# Fingerprint.net
KiCad netlist of a schematic drawn in EAGLE
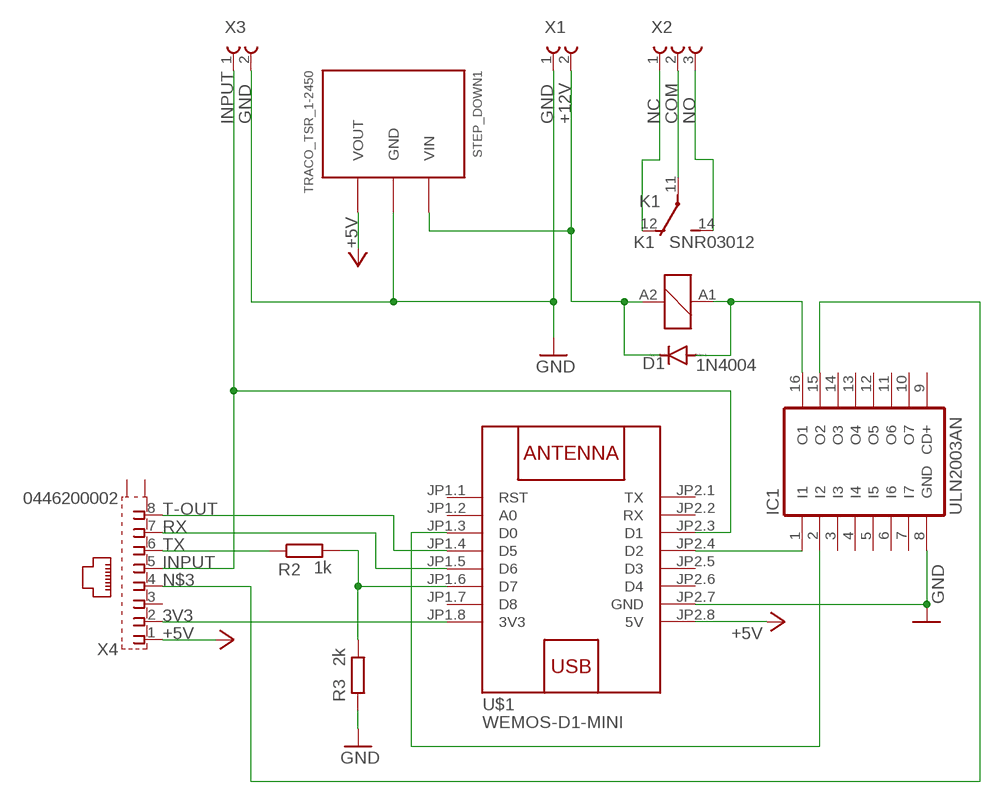
[diagram p0: schematic, sheet 1]

(export (version "E")
  (design (tool "Eeschema 10.0.6"))
  (components
    (comp (ref "D1")
      (value "1N4004")
      (footprint "eagle-import:DO41-10")
      (libsource (lib "eagle-import") (part "1N4004"))
    )
    (comp (ref "IC1")
      (value "ULN2003AN")
      (footprint "eagle-import:DIL16")
      (libsource (lib "eagle-import") (part "ULN2003AN"))
    )
    (comp (ref "K1")
      (value "SNR03012")
      (footprint "eagle-import:SNR-V")
      (libsource (lib "eagle-import") (part "SNR?03012"))
    )
    (comp (ref "R2")
      (value "1k")
      (footprint "eagle-import:0207_10")
      (libsource (lib "eagle-import") (part "R-EU_0207/10"))
    )
    (comp (ref "R3")
      (value "2k")
      (footprint "eagle-import:0207_10")
      (libsource (lib "eagle-import") (part "R-EU_0207/10"))
    )
    (comp (ref "STEP_DOWN1")
      (value "TRACO_TSR_1-2450")
      (footprint "eagle-import:TRACO_TSR_1-2450")
      (libsource (lib "eagle-import") (part "TRACO_TSR_1-2450"))
    )
    (comp (ref "U$1")
      (value "WEMOS-D1-MINI")
      (footprint "eagle-import:WEMOS-D1-MINI")
      (libsource (lib "eagle-import") (part "WEMOS-D1-MINI"))
    )
    (comp (ref "X1")
      (value "2PIN_5MM_TERMINAL")
      (footprint "eagle-import:2PIN_5MM_TERMMINAL")
      (libsource (lib "eagle-import") (part "2PIN_5MM_TERMINAL"))
    )
    (comp (ref "X2")
      (value "3PIN_5MM_TERMINAL")
      (footprint "eagle-import:3PIN_5MM_TERMINAL")
      (libsource (lib "eagle-import") (part "3PIN_5MM_TERMINAL"))
    )
    (comp (ref "X3")
      (value "2PIN_5MM_TERMINAL")
      (footprint "eagle-import:2PIN_5MM_TERMMINAL")
      (libsource (lib "eagle-import") (part "2PIN_5MM_TERMINAL"))
    )
    (comp (ref "X4")
      (value "0446200002")
      (footprint "eagle-import:0446200002")
      (fields (field (name "MF") "MOLEX"))
      (libsource (lib "eagle-import") (part "0446200002"))
    )
  )
  (nets
    (net (code "1") (name "+5V") (class "Default")
      (node (ref "STEP_DOWN1") (pin "VOUT") (pinfunction "VOUT_VOUT") (pintype "output"))
      (node (ref "U$1") (pin "JP2.8") (pinfunction "5V_JP2.8") (pintype "power_in"))
      (node (ref "X4") (pin "1") (pinfunction "1_1") (pintype "passive"))
    )
    (net (code "2") (name "/+12V") (class "Default")
      (node (ref "D1") (pin "C") (pinfunction "C_C") (pintype "passive"))
      (node (ref "K1") (pin "A2") (pinfunction "2_A2") (pintype "passive"))
      (node (ref "STEP_DOWN1") (pin "VIN") (pinfunction "VIN_VIN") (pintype "input"))
      (node (ref "X1") (pin "2") (pinfunction "2_2") (pintype "passive"))
    )
    (net (code "3") (name "/3V3") (class "Default")
      (node (ref "U$1") (pin "JP1.8") (pinfunction "3V3_JP1.8") (pintype "power_in"))
      (node (ref "X4") (pin "2") (pinfunction "2_2") (pintype "passive"))
    )
    (net (code "4") (name "/COM") (class "Default")
      (node (ref "K1") (pin "11") (pinfunction "P_11") (pintype "passive"))
      (node (ref "X2") (pin "2") (pinfunction "2_2") (pintype "passive"))
    )
    (net (code "5") (name "/INPUT") (class "Default")
      (node (ref "U$1") (pin "JP2.3") (pinfunction "D1_JP2.3") (pintype "bidirectional"))
      (node (ref "X3") (pin "1") (pinfunction "1_1") (pintype "passive"))
      (node (ref "X4") (pin "5") (pinfunction "5_5") (pintype "passive"))
    )
    (net (code "6") (name "/N$3") (class "Default")
      (node (ref "IC1") (pin "15") (pinfunction "O2_15") (pintype "open_collector"))
      (node (ref "X4") (pin "4") (pinfunction "4_4") (pintype "passive"))
    )
    (net (code "7") (name "/NC") (class "Default")
      (node (ref "K1") (pin "12") (pinfunction "O_12") (pintype "passive"))
      (node (ref "X2") (pin "1") (pinfunction "1_1") (pintype "passive"))
    )
    (net (code "8") (name "/NO") (class "Default")
      (node (ref "K1") (pin "14") (pinfunction "S_14") (pintype "passive"))
      (node (ref "X2") (pin "3") (pinfunction "3_3") (pintype "passive"))
    )
    (net (code "9") (name "/RX") (class "Default")
      (node (ref "U$1") (pin "JP1.5") (pinfunction "D6_JP1.5") (pintype "bidirectional"))
      (node (ref "X4") (pin "7") (pinfunction "7_7") (pintype "passive"))
    )
    (net (code "10") (name "/T-OUT") (class "Default")
      (node (ref "U$1") (pin "JP1.4") (pinfunction "D5_JP1.4") (pintype "bidirectional"))
      (node (ref "X4") (pin "8") (pinfunction "8_8") (pintype "passive"))
    )
    (net (code "11") (name "/TX") (class "Default")
      (node (ref "R2") (pin "1") (pinfunction "1_1") (pintype "passive"))
      (node (ref "X4") (pin "6") (pinfunction "6_6") (pintype "passive"))
    )
    (net (code "12") (name "GND") (class "Default")
      (node (ref "IC1") (pin "8") (pinfunction "GND_8") (pintype "power_in"))
      (node (ref "R3") (pin "2") (pinfunction "2_2") (pintype "passive"))
      (node (ref "STEP_DOWN1") (pin "GND") (pinfunction "GND_GND") (pintype "bidirectional"))
      (node (ref "U$1") (pin "JP2.7") (pinfunction "GND_JP2.7") (pintype "power_in"))
      (node (ref "X1") (pin "1") (pinfunction "1_1") (pintype "passive"))
      (node (ref "X3") (pin "2") (pinfunction "2_2") (pintype "passive"))
    )
    (net (code "13") (name "Net-(IC1-I1)") (class "Default")
      (node (ref "IC1") (pin "1") (pinfunction "I1_1") (pintype "input"))
      (node (ref "U$1") (pin "JP2.4") (pinfunction "D2_JP2.4") (pintype "bidirectional"))
    )
    (net (code "14") (name "Net-(IC1-I2)") (class "Default")
      (node (ref "IC1") (pin "2") (pinfunction "I2_2") (pintype "input"))
      (node (ref "U$1") (pin "JP1.3") (pinfunction "D0_JP1.3") (pintype "bidirectional"))
    )
    (net (code "15") (name "Net-(IC1-O1)") (class "Default")
      (node (ref "D1") (pin "A") (pinfunction "A_A") (pintype "passive"))
      (node (ref "IC1") (pin "16") (pinfunction "O1_16") (pintype "open_collector"))
      (node (ref "K1") (pin "A1") (pinfunction "1_A1") (pintype "passive"))
    )
    (net (code "16") (name "Net-(U$1-D7)") (class "Default")
      (node (ref "R2") (pin "2") (pinfunction "2_2") (pintype "passive"))
      (node (ref "R3") (pin "1") (pinfunction "1_1") (pintype "passive"))
      (node (ref "U$1") (pin "JP1.6") (pinfunction "D7_JP1.6") (pintype "bidirectional"))
    )
    (net (code "17") (name "unconnected-(IC1-CD+-Pad9)") (class "Default")
      (node (ref "IC1") (pin "9") (pinfunction "CD+_9") (pintype "passive"))
    )
    (net (code "18") (name "unconnected-(IC1-I3-Pad3)") (class "Default")
      (node (ref "IC1") (pin "3") (pinfunction "I3_3") (pintype "input"))
    )
    (net (code "19") (name "unconnected-(IC1-I4-Pad4)") (class "Default")
      (node (ref "IC1") (pin "4") (pinfunction "I4_4") (pintype "input"))
    )
    (net (code "20") (name "unconnected-(IC1-I5-Pad5)") (class "Default")
      (node (ref "IC1") (pin "5") (pinfunction "I5_5") (pintype "input"))
    )
    (net (code "21") (name "unconnected-(IC1-I6-Pad6)") (class "Default")
      (node (ref "IC1") (pin "6") (pinfunction "I6_6") (pintype "input"))
    )
    (net (code "22") (name "unconnected-(IC1-I7-Pad7)") (class "Default")
      (node (ref "IC1") (pin "7") (pinfunction "I7_7") (pintype "input"))
    )
    (net (code "23") (name "unconnected-(IC1-O3-Pad14)") (class "Default")
      (node (ref "IC1") (pin "14") (pinfunction "O3_14") (pintype "open_collector"))
    )
    (net (code "24") (name "unconnected-(IC1-O4-Pad13)") (class "Default")
      (node (ref "IC1") (pin "13") (pinfunction "O4_13") (pintype "open_collector"))
    )
    (net (code "25") (name "unconnected-(IC1-O5-Pad12)") (class "Default")
      (node (ref "IC1") (pin "12") (pinfunction "O5_12") (pintype "open_collector"))
    )
    (net (code "26") (name "unconnected-(IC1-O6-Pad11)") (class "Default")
      (node (ref "IC1") (pin "11") (pinfunction "O6_11") (pintype "open_collector"))
    )
    (net (code "27") (name "unconnected-(IC1-O7-Pad10)") (class "Default")
      (node (ref "IC1") (pin "10") (pinfunction "O7_10") (pintype "open_collector"))
    )
    (net (code "28") (name "unconnected-(U$1-A0-PadJP1.2)") (class "Default")
      (node (ref "U$1") (pin "JP1.2") (pinfunction "A0_JP1.2") (pintype "bidirectional"))
    )
    (net (code "29") (name "unconnected-(U$1-D3-PadJP2.5)") (class "Default")
      (node (ref "U$1") (pin "JP2.5") (pinfunction "D3_JP2.5") (pintype "bidirectional"))
    )
    (net (code "30") (name "unconnected-(U$1-D4-PadJP2.6)") (class "Default")
      (node (ref "U$1") (pin "JP2.6") (pinfunction "D4_JP2.6") (pintype "bidirectional"))
    )
    (net (code "31") (name "unconnected-(U$1-D8-PadJP1.7)") (class "Default")
      (node (ref "U$1") (pin "JP1.7") (pinfunction "D8_JP1.7") (pintype "bidirectional"))
    )
    (net (code "32") (name "unconnected-(U$1-RST-PadJP1.1)") (class "Default")
      (node (ref "U$1") (pin "JP1.1") (pinfunction "RST_JP1.1") (pintype "bidirectional"))
    )
    (net (code "33") (name "unconnected-(U$1-RX-PadJP2.2)") (class "Default")
      (node (ref "U$1") (pin "JP2.2") (pinfunction "RX_JP2.2") (pintype "bidirectional"))
    )
    (net (code "34") (name "unconnected-(U$1-TX-PadJP2.1)") (class "Default")
      (node (ref "U$1") (pin "JP2.1") (pinfunction "TX_JP2.1") (pintype "bidirectional"))
    )
    (net (code "35") (name "unconnected-(X4-Pad3)") (class "Default")
      (node (ref "X4") (pin "3") (pinfunction "3_3") (pintype "passive"))
    )
    (net (code "36") (name "unconnected-(X4-S1-PadS@1)") (class "Default")
      (node (ref "X4") (pin "S@1") (pinfunction "S1_S@1") (pintype "passive"))
    )
    (net (code "37") (name "unconnected-(X4-S2-PadS@2)") (class "Default")
      (node (ref "X4") (pin "S@2") (pinfunction "S2_S@2") (pintype "passive"))
    )
  )
)
